# 7segement4digits1badidea-mk-3-smd.net
KiCad netlist of a schematic drawn in EAGLE
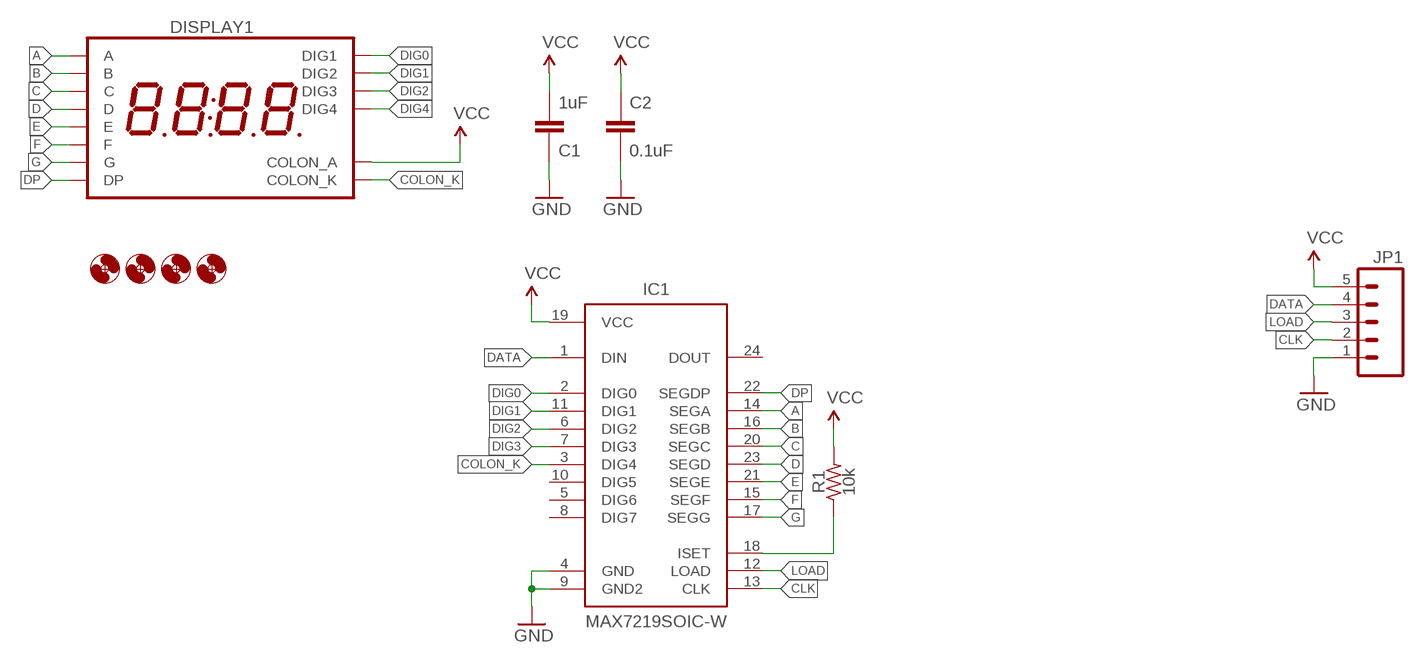
[diagram p0: schematic, sheet 1]

(export (version "E")
  (design (tool "Eeschema 10.0.6"))
  (components
    (comp (ref "C1")
      (value "1uF")
      (footprint "eagle-import:C0805")
      (libsource (lib "eagle-import") (part "CAPACITOR-CERAMICC0805"))
    )
    (comp (ref "C2")
      (value "0.1uF")
      (footprint "eagle-import:C0603")
      (libsource (lib "eagle-import") (part "CAPACITOR-CERAMICC0603"))
    )
    (comp (ref "DISPLAY1")
      (value "7SEG_4DIGIT_COLONLOLSMDWAT")
      (footprint "eagle-import:7SEG_4DIG_0.56IN_14MM_ADAFRUIT_LOL_SMD_WAT")
      (libsource (lib "eagle-import") (part "7SEG_4DIGIT_COLONLOLSMDWAT"))
    )
    (comp (ref "H1")
      (value "HOLE#2")
      (footprint "eagle-import:HOLE-#2")
      (libsource (lib "eagle-import") (part "HOLE#2"))
    )
    (comp (ref "H2")
      (value "HOLE#2")
      (footprint "eagle-import:HOLE-#2")
      (libsource (lib "eagle-import") (part "HOLE#2"))
    )
    (comp (ref "H3")
      (value "HOLE#2")
      (footprint "eagle-import:HOLE-#2")
      (libsource (lib "eagle-import") (part "HOLE#2"))
    )
    (comp (ref "H4")
      (value "HOLE#2")
      (footprint "eagle-import:HOLE-#2")
      (libsource (lib "eagle-import") (part "HOLE#2"))
    )
    (comp (ref "IC1")
      (value "MAX7219SOIC-W")
      (footprint "eagle-import:SO24W")
      (libsource (lib "eagle-import") (part "MAX7219SOIC-W"))
    )
    (comp (ref "JP1")
      (value "M05JST-PH-VERT-PTH")
      (footprint "eagle-import:JST-5-PH-VERT-PTH")
      (libsource (lib "eagle-import") (part "M05JST-PH-VERT-PTH"))
    )
    (comp (ref "R1")
      (value "10k")
      (footprint "eagle-import:R0603")
      (libsource (lib "eagle-import") (part "RESISTORR0603"))
    )
  )
  (nets
    (net (code "1") (name "A") (class "Default")
      (node (ref "DISPLAY1") (pin "P$13") (pinfunction "A_P$13") (pintype "passive"))
      (node (ref "IC1") (pin "14") (pinfunction "SEGA_14") (pintype "bidirectional"))
    )
    (net (code "2") (name "B") (class "Default")
      (node (ref "DISPLAY1") (pin "P$9") (pinfunction "B_P$9") (pintype "passive"))
      (node (ref "IC1") (pin "16") (pinfunction "SEGB_16") (pintype "bidirectional"))
    )
    (net (code "3") (name "C") (class "Default")
      (node (ref "DISPLAY1") (pin "P$4") (pinfunction "C_P$4") (pintype "passive"))
      (node (ref "IC1") (pin "20") (pinfunction "SEGC_20") (pintype "bidirectional"))
    )
    (net (code "4") (name "CLK") (class "Default")
      (node (ref "IC1") (pin "13") (pinfunction "CLK_13") (pintype "bidirectional"))
      (node (ref "JP1") (pin "2") (pinfunction "2_2") (pintype "passive"))
    )
    (net (code "5") (name "COLON_K") (class "Default")
      (node (ref "DISPLAY1") (pin "P$7") (pinfunction "COLON_K_P$7") (pintype "passive"))
      (node (ref "IC1") (pin "3") (pinfunction "DIG4_3") (pintype "bidirectional"))
    )
    (net (code "6") (name "D") (class "Default")
      (node (ref "DISPLAY1") (pin "P$2") (pinfunction "D_P$2") (pintype "passive"))
      (node (ref "IC1") (pin "23") (pinfunction "SEGD_23") (pintype "bidirectional"))
    )
    (net (code "7") (name "DATA") (class "Default")
      (node (ref "IC1") (pin "1") (pinfunction "DIN_1") (pintype "bidirectional"))
      (node (ref "JP1") (pin "4") (pinfunction "4_4") (pintype "passive"))
    )
    (net (code "8") (name "DIG0") (class "Default")
      (node (ref "DISPLAY1") (pin "P$14") (pinfunction "DIG1_P$14") (pintype "passive"))
      (node (ref "IC1") (pin "2") (pinfunction "DIG0_2") (pintype "bidirectional"))
    )
    (net (code "9") (name "DIG1") (class "Default")
      (node (ref "DISPLAY1") (pin "P$11") (pinfunction "DIG2_P$11") (pintype "passive"))
      (node (ref "IC1") (pin "11") (pinfunction "DIG1_11") (pintype "bidirectional"))
    )
    (net (code "10") (name "DIG2") (class "Default")
      (node (ref "DISPLAY1") (pin "P$10") (pinfunction "DIG3_P$10") (pintype "passive"))
      (node (ref "IC1") (pin "6") (pinfunction "DIG2_6") (pintype "bidirectional"))
    )
    (net (code "11") (name "DIG3") (class "Default")
      (node (ref "IC1") (pin "7") (pinfunction "DIG3_7") (pintype "bidirectional"))
    )
    (net (code "12") (name "DIG4") (class "Default")
      (node (ref "DISPLAY1") (pin "P$6") (pinfunction "DIG4_P$6") (pintype "passive"))
    )
    (net (code "13") (name "DP") (class "Default")
      (node (ref "DISPLAY1") (pin "P$3") (pinfunction "DP_P$3") (pintype "passive"))
      (node (ref "IC1") (pin "22") (pinfunction "SEGDP_22") (pintype "bidirectional"))
    )
    (net (code "14") (name "E") (class "Default")
      (node (ref "DISPLAY1") (pin "P$1") (pinfunction "E_P$1") (pintype "passive"))
      (node (ref "IC1") (pin "21") (pinfunction "SEGE_21") (pintype "bidirectional"))
    )
    (net (code "15") (name "F") (class "Default")
      (node (ref "DISPLAY1") (pin "P$12") (pinfunction "F_P$12") (pintype "passive"))
      (node (ref "IC1") (pin "15") (pinfunction "SEGF_15") (pintype "bidirectional"))
    )
    (net (code "16") (name "G") (class "Default")
      (node (ref "DISPLAY1") (pin "P$5") (pinfunction "G_P$5") (pintype "passive"))
      (node (ref "IC1") (pin "17") (pinfunction "SEGG_17") (pintype "bidirectional"))
    )
    (net (code "17") (name "GND") (class "Default")
      (node (ref "C1") (pin "1") (pinfunction "1_1") (pintype "passive"))
      (node (ref "C2") (pin "2") (pinfunction "2_2") (pintype "passive"))
      (node (ref "IC1") (pin "4") (pinfunction "GND_4") (pintype "bidirectional"))
      (node (ref "IC1") (pin "9") (pinfunction "GND2_9") (pintype "bidirectional"))
      (node (ref "JP1") (pin "1") (pinfunction "1_1") (pintype "passive"))
    )
    (net (code "18") (name "LOAD") (class "Default")
      (node (ref "IC1") (pin "12") (pinfunction "LOAD_12") (pintype "bidirectional"))
      (node (ref "JP1") (pin "3") (pinfunction "3_3") (pintype "passive"))
    )
    (net (code "19") (name "Net-(IC1-ISET)") (class "Default")
      (node (ref "IC1") (pin "18") (pinfunction "ISET_18") (pintype "bidirectional"))
      (node (ref "R1") (pin "1") (pinfunction "1_1") (pintype "passive"))
    )
    (net (code "20") (name "VCC") (class "Default")
      (node (ref "C1") (pin "2") (pinfunction "2_2") (pintype "passive"))
      (node (ref "C2") (pin "1") (pinfunction "1_1") (pintype "passive"))
      (node (ref "DISPLAY1") (pin "P$8") (pinfunction "COLON_A_P$8") (pintype "passive"))
      (node (ref "IC1") (pin "19") (pinfunction "VCC_19") (pintype "bidirectional"))
      (node (ref "JP1") (pin "5") (pinfunction "5_5") (pintype "passive"))
      (node (ref "R1") (pin "2") (pinfunction "2_2") (pintype "passive"))
    )
    (net (code "21") (name "unconnected-(IC1-DIG5-Pad10)") (class "Default")
      (node (ref "IC1") (pin "10") (pinfunction "DIG5_10") (pintype "bidirectional"))
    )
    (net (code "22") (name "unconnected-(IC1-DIG6-Pad5)") (class "Default")
      (node (ref "IC1") (pin "5") (pinfunction "DIG6_5") (pintype "bidirectional"))
    )
    (net (code "23") (name "unconnected-(IC1-DIG7-Pad8)") (class "Default")
      (node (ref "IC1") (pin "8") (pinfunction "DIG7_8") (pintype "bidirectional"))
    )
    (net (code "24") (name "unconnected-(IC1-DOUT-Pad24)") (class "Default")
      (node (ref "IC1") (pin "24") (pinfunction "DOUT_24") (pintype "bidirectional"))
    )
  )
)
